# ftdi.net
KiCad netlist of a schematic drawn in EAGLE
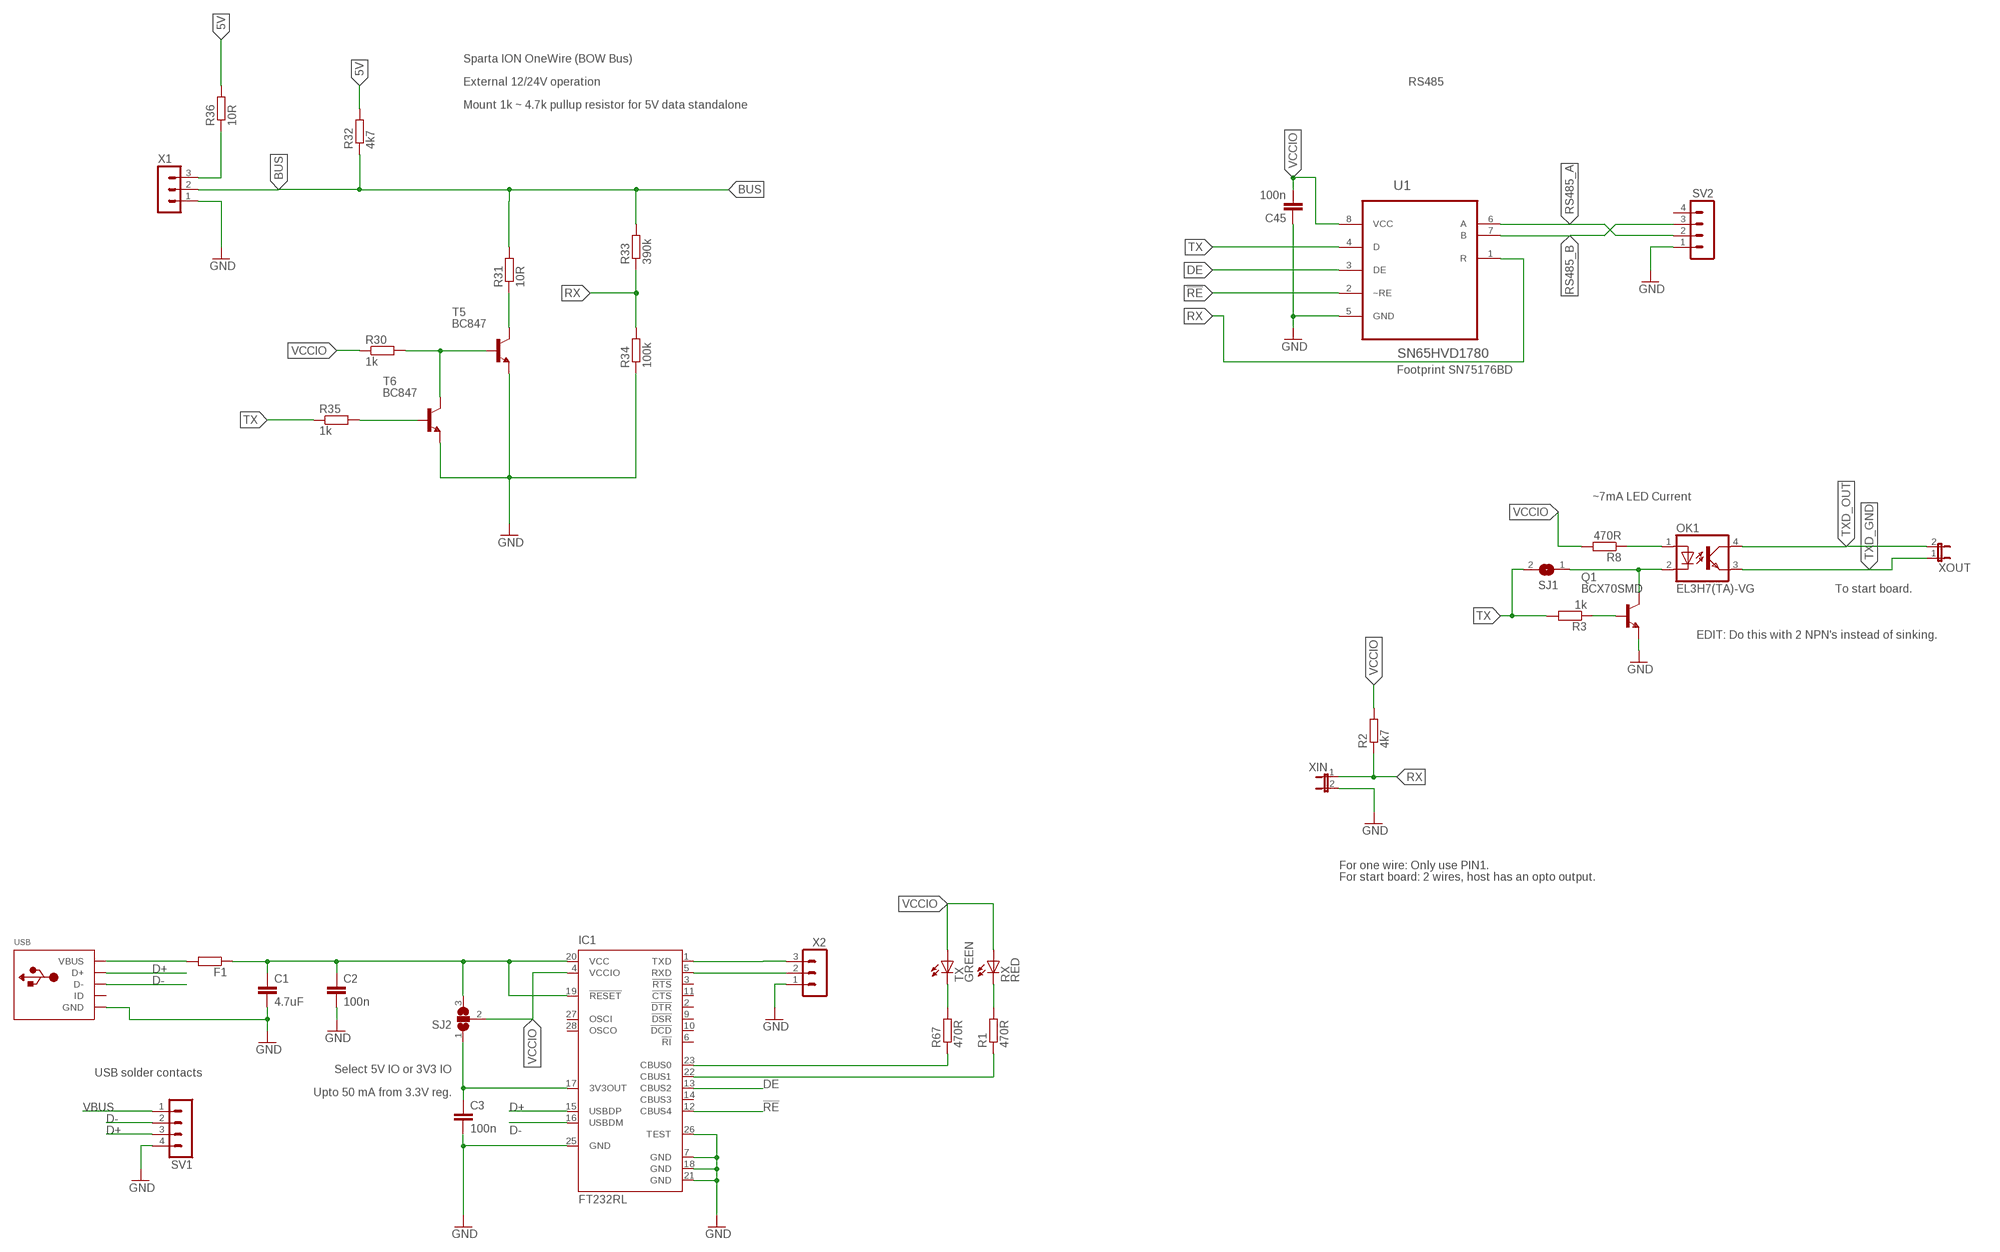
[diagram p0: schematic, sheet 1]

(export (version "E")
  (design (tool "Eeschema 10.0.6"))
  (components
    (comp (ref "C1")
      (value "4.7uF")
      (footprint "eagle-import:C0805")
      (libsource (lib "eagle-import") (part "C-EUC0805"))
    )
    (comp (ref "C2")
      (value "100n")
      (footprint "eagle-import:C0805")
      (libsource (lib "eagle-import") (part "C-EUC0805"))
    )
    (comp (ref "C3")
      (value "100n")
      (footprint "eagle-import:C0805")
      (libsource (lib "eagle-import") (part "C-EUC0805"))
    )
    (comp (ref "C45")
      (value "100n")
      (footprint "eagle-import:C0805")
      (libsource (lib "eagle-import") (part "C-EUC0805"))
    )
    (comp (ref "F1")
      (value "R-EU_R0805")
      (footprint "eagle-import:R0805")
      (libsource (lib "eagle-import") (part "R-EU_R0805"))
    )
    (comp (ref "IC1")
      (value "FT232RL")
      (footprint "eagle-import:SSOP28")
      (libsource (lib "eagle-import") (part "FT232RL"))
    )
    (comp (ref "OK1")
      (value "EL3H7(TA)-VG")
      (footprint "eagle-import:MINI-FLAT-4")
      (libsource (lib "eagle-import") (part "TLP283"))
    )
    (comp (ref "Q1")
      (value "BCX70SMD")
      (footprint "eagle-import:SOT23")
      (libsource (lib "eagle-import") (part "BCX70SMD"))
    )
    (comp (ref "R1")
      (value "470R")
      (footprint "eagle-import:M0805")
      (libsource (lib "eagle-import") (part "R-EU_M0805"))
    )
    (comp (ref "R2")
      (value "4k7")
      (footprint "eagle-import:R0805")
      (libsource (lib "eagle-import") (part "R-EU_R0805"))
    )
    (comp (ref "R3")
      (value "1k")
      (footprint "eagle-import:R0805")
      (libsource (lib "eagle-import") (part "R-EU_R0805"))
    )
    (comp (ref "R8")
      (value "470R")
      (footprint "eagle-import:R0805")
      (libsource (lib "eagle-import") (part "R-EU_R0805"))
    )
    (comp (ref "R30")
      (value "1k")
      (footprint "eagle-import:M0805")
      (libsource (lib "eagle-import") (part "R-EU_M0805"))
    )
    (comp (ref "R31")
      (value "10R")
      (footprint "eagle-import:M0805")
      (libsource (lib "eagle-import") (part "R-EU_M0805"))
    )
    (comp (ref "R32")
      (value "4k7")
      (footprint "eagle-import:M0805")
      (libsource (lib "eagle-import") (part "R-EU_M0805"))
    )
    (comp (ref "R33")
      (value "390k")
      (footprint "eagle-import:M0805")
      (libsource (lib "eagle-import") (part "R-EU_M0805"))
    )
    (comp (ref "R34")
      (value "100k")
      (footprint "eagle-import:M0805")
      (libsource (lib "eagle-import") (part "R-EU_M0805"))
    )
    (comp (ref "R35")
      (value "1k")
      (footprint "eagle-import:M0805")
      (libsource (lib "eagle-import") (part "R-EU_M0805"))
    )
    (comp (ref "R36")
      (value "10R")
      (footprint "eagle-import:M0805")
      (libsource (lib "eagle-import") (part "R-EU_M0805"))
    )
    (comp (ref "R67")
      (value "470R")
      (footprint "eagle-import:M0805")
      (libsource (lib "eagle-import") (part "R-EU_M0805"))
    )
    (comp (ref "RX")
      (value "RED")
      (footprint "eagle-import:CHIPLED_0805")
      (libsource (lib "eagle-import") (part "LEDCHIPLED_0805"))
    )
    (comp (ref "SJ1") (value "SJ") (footprint "eagle-import:SJ") (libsource (lib "eagle-import") (part "SJ")))
    (comp (ref "SJ2")
      (value "SJ2W")
      (footprint "eagle-import:SJ_2")
      (libsource (lib "eagle-import") (part "SJ2W"))
    )
    (comp (ref "SV1")
      (value "MA04-1")
      (footprint "eagle-import:MA04-1")
      (libsource (lib "eagle-import") (part "MA04-1"))
    )
    (comp (ref "SV2")
      (value "MA04-1")
      (footprint "eagle-import:MA04-1")
      (fields (field (name "OC_FARNELL") "unknown") (field (name "OC_NEWARK") "unknown"))
      (libsource (lib "eagle-import") (part "MA04-1"))
    )
    (comp (ref "T5")
      (value "BC847")
      (footprint "eagle-import:SOT23")
      (libsource (lib "eagle-import") (part "BC847"))
    )
    (comp (ref "T6")
      (value "BC847")
      (footprint "eagle-import:SOT23")
      (libsource (lib "eagle-import") (part "BC847"))
    )
    (comp (ref "TX")
      (value "GREEN")
      (footprint "eagle-import:CHIPLED_0805")
      (libsource (lib "eagle-import") (part "LEDCHIPLED_0805"))
    )
    (comp (ref "U1")
      (value "SN65HVD1780")
      (footprint "eagle-import:SOIC127P600X175-8N")
      (fields (field (name "MPN") "SN75176BD"))
      (libsource (lib "eagle-import") (part "SN75176BD"))
    )
    (comp (ref "USB")
      (value "ADAFRUIT_USBMINIB")
      (footprint "eagle-import:ADAFRUIT_USB-MINIB")
      (libsource (lib "eagle-import") (part "ADAFRUIT_USBMINIB"))
    )
    (comp (ref "X1")
      (value "MA03-1")
      (footprint "eagle-import:MA03-1")
      (fields (field (name "OC_FARNELL") "unknown") (field (name "OC_NEWARK") "unknown"))
      (libsource (lib "eagle-import") (part "MA03-1"))
    )
    (comp (ref "X2")
      (value "MA03-1")
      (footprint "eagle-import:MA03-1")
      (fields (field (name "OC_FARNELL") "unknown") (field (name "OC_NEWARK") "unknown"))
      (libsource (lib "eagle-import") (part "MA03-1"))
    )
    (comp (ref "XIN")
      (value "JP1E")
      (footprint "eagle-import:JP1")
      (libsource (lib "eagle-import") (part "JP1E"))
    )
    (comp (ref "XOUT")
      (value "JP1E")
      (footprint "eagle-import:JP1")
      (libsource (lib "eagle-import") (part "JP1E"))
    )
  )
  (nets
    (net (code "1") (name "/D+") (class "Default")
      (node (ref "IC1") (pin "15") (pinfunction "USBDP_15") (pintype "bidirectional"))
      (node (ref "SV1") (pin "3") (pinfunction "3_3") (pintype "passive"))
      (node (ref "USB") (pin "D+") (pinfunction "D+_D+") (pintype "bidirectional"))
    )
    (net (code "2") (name "/D-") (class "Default")
      (node (ref "IC1") (pin "16") (pinfunction "USBDM_16") (pintype "bidirectional"))
      (node (ref "SV1") (pin "2") (pinfunction "2_2") (pintype "passive"))
      (node (ref "USB") (pin "D-") (pinfunction "D-_D-") (pintype "bidirectional"))
    )
    (net (code "3") (name "/VBUS") (class "Default")
      (node (ref "F1") (pin "2") (pinfunction "2_2") (pintype "passive"))
      (node (ref "SV1") (pin "1") (pinfunction "1_1") (pintype "passive"))
      (node (ref "USB") (pin "VBUS") (pinfunction "VBUS_VBUS") (pintype "power_in"))
    )
    (net (code "4") (name "/~{RE}") (class "Default")
      (node (ref "IC1") (pin "12") (pinfunction "CBUS4_12") (pintype "bidirectional"))
      (node (ref "U1") (pin "2") (pinfunction "~{RE}_2") (pintype "input"))
    )
    (net (code "5") (name "5V") (class "Default")
      (node (ref "C1") (pin "1") (pinfunction "1_1") (pintype "passive"))
      (node (ref "C2") (pin "1") (pinfunction "1_1") (pintype "passive"))
      (node (ref "F1") (pin "1") (pinfunction "1_1") (pintype "passive"))
      (node (ref "IC1") (pin "19") (pinfunction "~{RESET}_19") (pintype "input"))
      (node (ref "IC1") (pin "20") (pinfunction "VCC_20") (pintype "power_in"))
      (node (ref "R32") (pin "2") (pinfunction "2_2") (pintype "passive"))
      (node (ref "R36") (pin "2") (pinfunction "2_2") (pintype "passive"))
      (node (ref "SJ2") (pin "3") (pinfunction "3_3") (pintype "passive"))
    )
    (net (code "6") (name "BUS") (class "Default")
      (node (ref "R31") (pin "2") (pinfunction "2_2") (pintype "passive"))
      (node (ref "R32") (pin "1") (pinfunction "1_1") (pintype "passive"))
      (node (ref "R33") (pin "2") (pinfunction "2_2") (pintype "passive"))
      (node (ref "X1") (pin "2") (pinfunction "2_2") (pintype "passive"))
    )
    (net (code "7") (name "DE") (class "Default")
      (node (ref "IC1") (pin "13") (pinfunction "CBUS2_13") (pintype "bidirectional"))
      (node (ref "U1") (pin "3") (pinfunction "DE_3") (pintype "input"))
    )
    (net (code "8") (name "GND") (class "Default")
      (node (ref "C1") (pin "2") (pinfunction "2_2") (pintype "passive"))
      (node (ref "C2") (pin "2") (pinfunction "2_2") (pintype "passive"))
      (node (ref "C3") (pin "2") (pinfunction "2_2") (pintype "passive"))
      (node (ref "C45") (pin "1") (pinfunction "1_1") (pintype "passive"))
      (node (ref "IC1") (pin "18") (pinfunction "GND_18") (pintype "power_in"))
      (node (ref "IC1") (pin "21") (pinfunction "GND_21") (pintype "power_in"))
      (node (ref "IC1") (pin "25") (pinfunction "GND_25") (pintype "power_in"))
      (node (ref "IC1") (pin "26") (pinfunction "TEST_26") (pintype "input"))
      (node (ref "IC1") (pin "7") (pinfunction "GND_7") (pintype "power_in"))
      (node (ref "Q1") (pin "2") (pinfunction "E_2") (pintype "passive"))
      (node (ref "R34") (pin "1") (pinfunction "1_1") (pintype "passive"))
      (node (ref "SV1") (pin "4") (pinfunction "4_4") (pintype "passive"))
      (node (ref "SV2") (pin "1") (pinfunction "1_1") (pintype "passive"))
      (node (ref "T5") (pin "2") (pinfunction "E_2") (pintype "passive"))
      (node (ref "T6") (pin "2") (pinfunction "E_2") (pintype "passive"))
      (node (ref "U1") (pin "5") (pinfunction "GND_5") (pintype "passive"))
      (node (ref "USB") (pin "GND") (pinfunction "GND_GND") (pintype "power_in"))
      (node (ref "X1") (pin "1") (pinfunction "1_1") (pintype "passive"))
      (node (ref "X2") (pin "1") (pinfunction "1_1") (pintype "passive"))
      (node (ref "XIN") (pin "2") (pinfunction "2_2") (pintype "passive"))
    )
    (net (code "9") (name "Net-(IC1-3V3OUT)") (class "Default")
      (node (ref "C3") (pin "1") (pinfunction "1_1") (pintype "passive"))
      (node (ref "IC1") (pin "17") (pinfunction "3V3OUT_17") (pintype "output"))
      (node (ref "SJ2") (pin "1") (pinfunction "1_1") (pintype "passive"))
    )
    (net (code "10") (name "Net-(IC1-CBUS0)") (class "Default")
      (node (ref "IC1") (pin "23") (pinfunction "CBUS0_23") (pintype "bidirectional"))
      (node (ref "R67") (pin "1") (pinfunction "1_1") (pintype "passive"))
    )
    (net (code "11") (name "Net-(IC1-CBUS1)") (class "Default")
      (node (ref "IC1") (pin "22") (pinfunction "CBUS1_22") (pintype "bidirectional"))
      (node (ref "R1") (pin "1") (pinfunction "1_1") (pintype "passive"))
    )
    (net (code "12") (name "Net-(OK1-A)") (class "Default")
      (node (ref "OK1") (pin "1") (pinfunction "A_1") (pintype "passive"))
      (node (ref "R8") (pin "1") (pinfunction "1_1") (pintype "passive"))
    )
    (net (code "13") (name "Net-(OK1-C)") (class "Default")
      (node (ref "OK1") (pin "2") (pinfunction "C_2") (pintype "passive"))
      (node (ref "Q1") (pin "3") (pinfunction "C_3") (pintype "passive"))
      (node (ref "SJ1") (pin "1") (pinfunction "1_1") (pintype "passive"))
    )
    (net (code "14") (name "Net-(Q1-B)") (class "Default")
      (node (ref "Q1") (pin "1") (pinfunction "B_1") (pintype "passive"))
      (node (ref "R3") (pin "1") (pinfunction "1_1") (pintype "passive"))
    )
    (net (code "15") (name "Net-(R1-Pad2)") (class "Default")
      (node (ref "R1") (pin "2") (pinfunction "2_2") (pintype "passive"))
      (node (ref "RX") (pin "C") (pinfunction "C_C") (pintype "passive"))
    )
    (net (code "16") (name "Net-(R36-Pad1)") (class "Default")
      (node (ref "R36") (pin "1") (pinfunction "1_1") (pintype "passive"))
      (node (ref "X1") (pin "3") (pinfunction "3_3") (pintype "passive"))
    )
    (net (code "17") (name "Net-(R67-Pad2)") (class "Default")
      (node (ref "R67") (pin "2") (pinfunction "2_2") (pintype "passive"))
      (node (ref "TX") (pin "C") (pinfunction "C_C") (pintype "passive"))
    )
    (net (code "18") (name "Net-(T5-B)") (class "Default")
      (node (ref "R30") (pin "2") (pinfunction "2_2") (pintype "passive"))
      (node (ref "T5") (pin "1") (pinfunction "B_1") (pintype "passive"))
      (node (ref "T6") (pin "3") (pinfunction "C_3") (pintype "passive"))
    )
    (net (code "19") (name "Net-(T5-C)") (class "Default")
      (node (ref "R31") (pin "1") (pinfunction "1_1") (pintype "passive"))
      (node (ref "T5") (pin "3") (pinfunction "C_3") (pintype "passive"))
    )
    (net (code "20") (name "Net-(T6-B)") (class "Default")
      (node (ref "R35") (pin "2") (pinfunction "2_2") (pintype "passive"))
      (node (ref "T6") (pin "1") (pinfunction "B_1") (pintype "passive"))
    )
    (net (code "21") (name "RS485_A") (class "Default")
      (node (ref "SV2") (pin "2") (pinfunction "2_2") (pintype "passive"))
      (node (ref "U1") (pin "6") (pinfunction "A_6") (pintype "output"))
    )
    (net (code "22") (name "RS485_B") (class "Default")
      (node (ref "SV2") (pin "3") (pinfunction "3_3") (pintype "passive"))
      (node (ref "U1") (pin "7") (pinfunction "B_7") (pintype "output"))
    )
    (net (code "23") (name "RX") (class "Default")
      (node (ref "IC1") (pin "5") (pinfunction "RXD_5") (pintype "input"))
      (node (ref "R2") (pin "1") (pinfunction "1_1") (pintype "passive"))
      (node (ref "R33") (pin "1") (pinfunction "1_1") (pintype "passive"))
      (node (ref "R34") (pin "2") (pinfunction "2_2") (pintype "passive"))
      (node (ref "U1") (pin "1") (pinfunction "R_1") (pintype "output"))
      (node (ref "X2") (pin "2") (pinfunction "2_2") (pintype "passive"))
      (node (ref "XIN") (pin "1") (pinfunction "1_1") (pintype "passive"))
    )
    (net (code "24") (name "TX") (class "Default")
      (node (ref "IC1") (pin "1") (pinfunction "TXD_1") (pintype "output"))
      (node (ref "R3") (pin "2") (pinfunction "2_2") (pintype "passive"))
      (node (ref "R35") (pin "1") (pinfunction "1_1") (pintype "passive"))
      (node (ref "SJ1") (pin "2") (pinfunction "2_2") (pintype "passive"))
      (node (ref "U1") (pin "4") (pinfunction "D_4") (pintype "input"))
      (node (ref "X2") (pin "3") (pinfunction "3_3") (pintype "passive"))
    )
    (net (code "25") (name "TXD_GND") (class "Default")
      (node (ref "OK1") (pin "3") (pinfunction "EMIT_3") (pintype "passive"))
      (node (ref "XOUT") (pin "1") (pinfunction "1_1") (pintype "passive"))
    )
    (net (code "26") (name "TXD_OUT") (class "Default")
      (node (ref "OK1") (pin "4") (pinfunction "COL_4") (pintype "passive"))
      (node (ref "XOUT") (pin "2") (pinfunction "2_2") (pintype "passive"))
    )
    (net (code "27") (name "VCCIO") (class "Default")
      (node (ref "C45") (pin "2") (pinfunction "2_2") (pintype "passive"))
      (node (ref "IC1") (pin "4") (pinfunction "VCCIO_4") (pintype "power_in"))
      (node (ref "R2") (pin "2") (pinfunction "2_2") (pintype "passive"))
      (node (ref "R30") (pin "1") (pinfunction "1_1") (pintype "passive"))
      (node (ref "R8") (pin "2") (pinfunction "2_2") (pintype "passive"))
      (node (ref "RX") (pin "A") (pinfunction "A_A") (pintype "passive"))
      (node (ref "SJ2") (pin "2") (pinfunction "2_2") (pintype "passive"))
      (node (ref "TX") (pin "A") (pinfunction "A_A") (pintype "passive"))
      (node (ref "U1") (pin "8") (pinfunction "VCC_8") (pintype "power_in"))
    )
    (net (code "28") (name "unconnected-(IC1-CBUS3-Pad14)") (class "Default")
      (node (ref "IC1") (pin "14") (pinfunction "CBUS3_14") (pintype "bidirectional"))
    )
    (net (code "29") (name "unconnected-(IC1-OSCI-Pad27)") (class "Default")
      (node (ref "IC1") (pin "27") (pinfunction "OSCI_27") (pintype "input"))
    )
    (net (code "30") (name "unconnected-(IC1-OSCO-Pad28)") (class "Default")
      (node (ref "IC1") (pin "28") (pinfunction "OSCO_28") (pintype "output"))
    )
    (net (code "31") (name "unconnected-(IC1-~{CTS}-Pad11)") (class "Default")
      (node (ref "IC1") (pin "11") (pinfunction "~{CTS}_11") (pintype "input"))
    )
    (net (code "32") (name "unconnected-(IC1-~{DCD}-Pad10)") (class "Default")
      (node (ref "IC1") (pin "10") (pinfunction "~{DCD}_10") (pintype "input"))
    )
    (net (code "33") (name "unconnected-(IC1-~{DSR}-Pad9)") (class "Default")
      (node (ref "IC1") (pin "9") (pinfunction "~{DSR}_9") (pintype "input"))
    )
    (net (code "34") (name "unconnected-(IC1-~{DTR}-Pad2)") (class "Default")
      (node (ref "IC1") (pin "2") (pinfunction "~{DTR}_2") (pintype "output"))
    )
    (net (code "35") (name "unconnected-(IC1-~{RI}-Pad6)") (class "Default")
      (node (ref "IC1") (pin "6") (pinfunction "~{RI}_6") (pintype "input"))
    )
    (net (code "36") (name "unconnected-(IC1-~{RTS}-Pad3)") (class "Default")
      (node (ref "IC1") (pin "3") (pinfunction "~{RTS}_3") (pintype "output"))
    )
    (net (code "37") (name "unconnected-(SV2-Pad4)") (class "Default")
      (node (ref "SV2") (pin "4") (pinfunction "4_4") (pintype "passive"))
    )
    (net (code "38") (name "unconnected-(USB-PadID)") (class "Default")
      (node (ref "USB") (pin "ID") (pinfunction "ID_ID") (pintype "bidirectional"))
    )
  )
)
